# G17_Sensor_V2.net
KiCad netlist of a schematic drawn in EAGLE
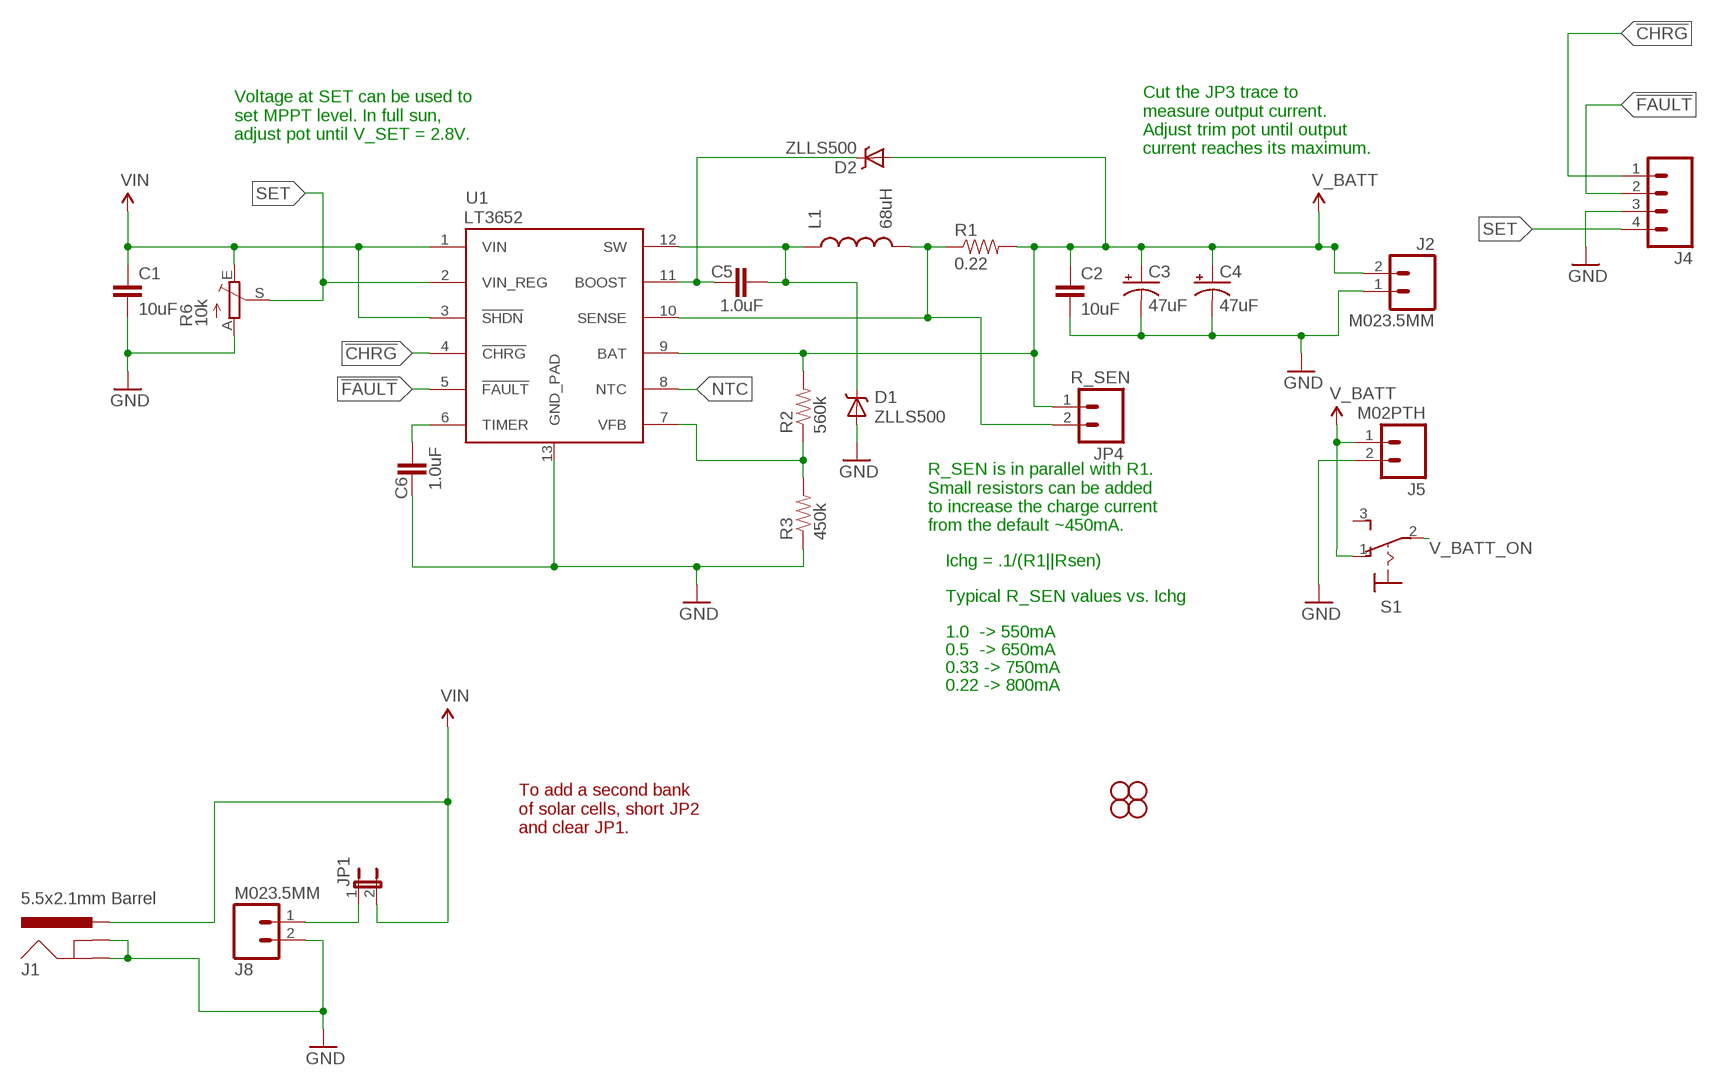
[diagram p0: schematic, sheet 1]
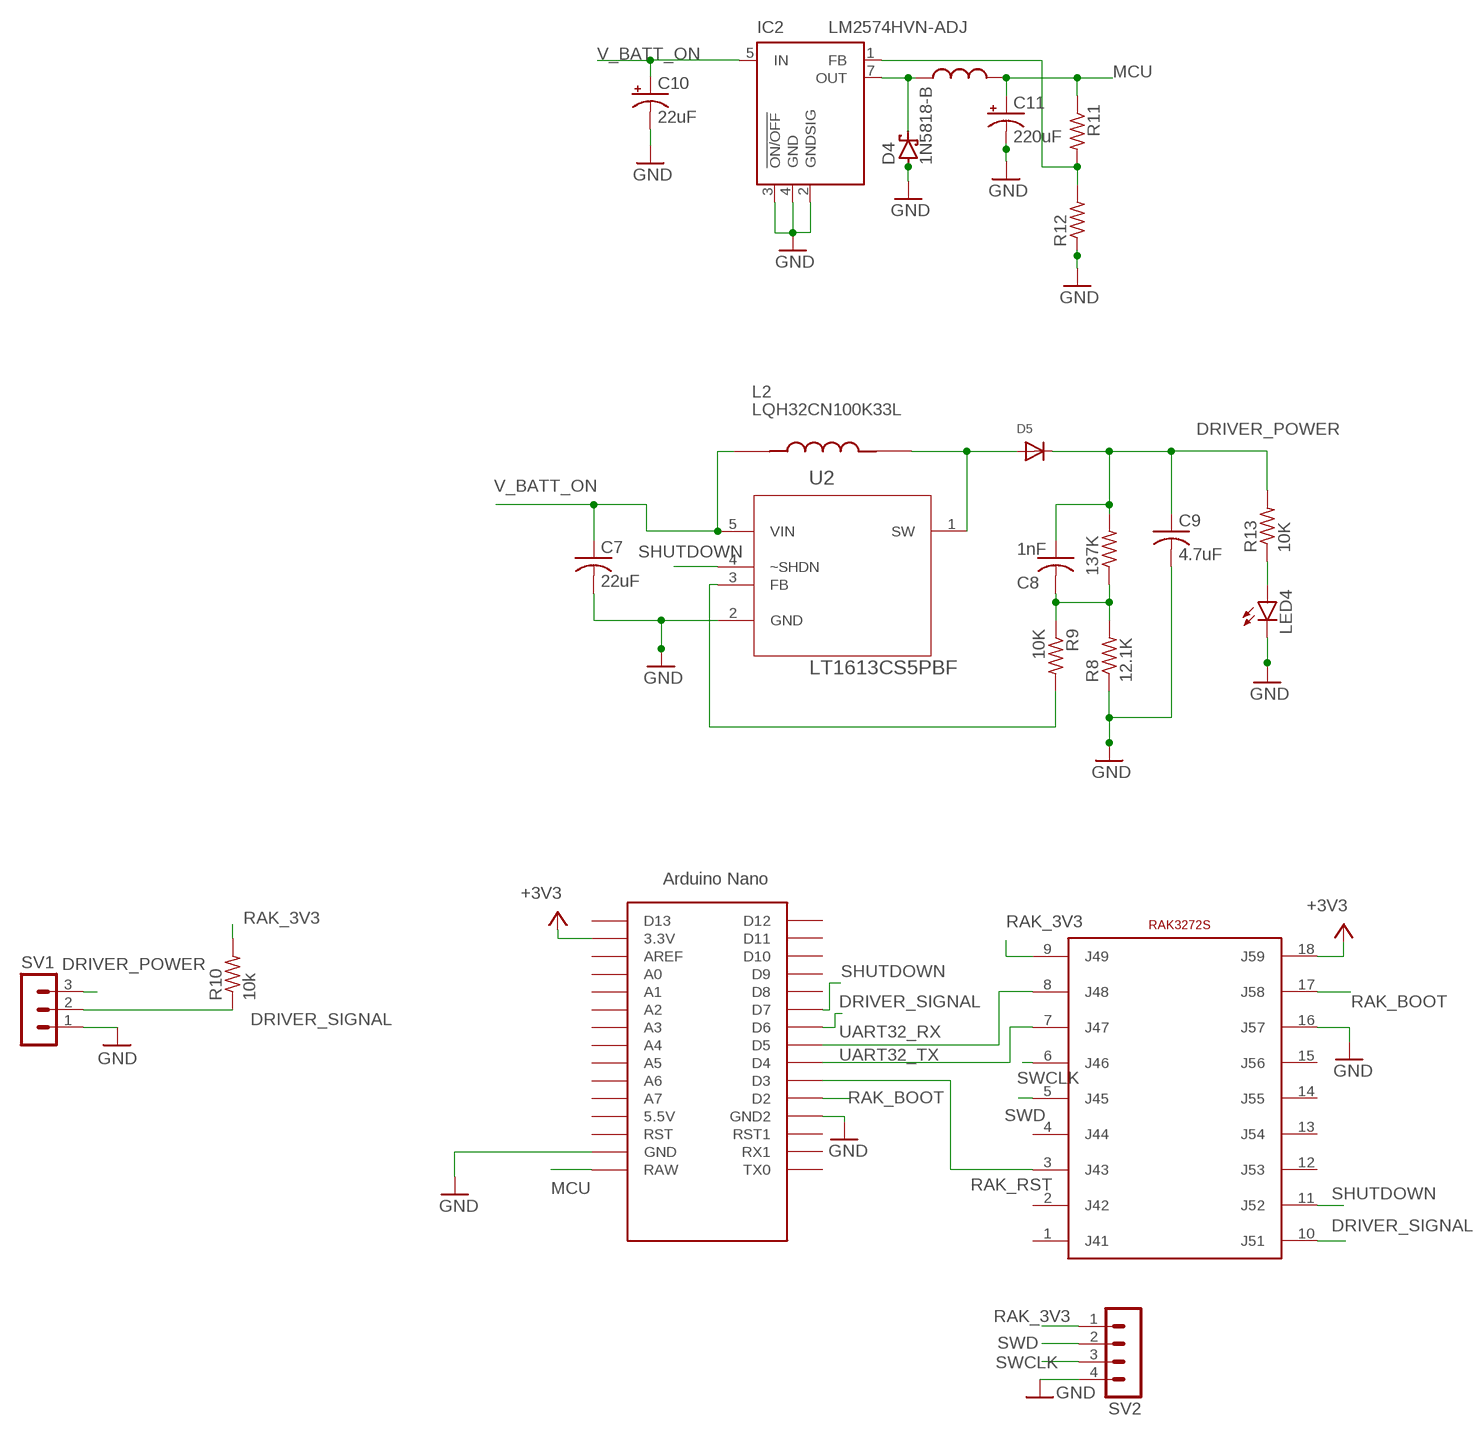
[diagram p1: schematic, sheet 2]

(export (version "E")
  (design (tool "Eeschema 10.0.6"))
  (components
    (comp (ref "137K")
      (value "R-US_R0805")
      (footprint "eagle-import:R0805")
      (libsource (lib "eagle-import") (part "R-US_R0805"))
    )
    (comp (ref "C7")
      (value "22uF")
      (footprint "eagle-import:C0805")
      (libsource (lib "eagle-import") (part "C-USC0805"))
    )
    (comp (ref "C8")
      (value "1nF")
      (footprint "eagle-import:C0805")
      (libsource (lib "eagle-import") (part "C-USC0805"))
    )
    (comp (ref "C9")
      (value "4.7uF")
      (footprint "eagle-import:C1206")
      (libsource (lib "eagle-import") (part "C-USC1206"))
    )
    (comp (ref "C10")
      (value "22uF")
      (footprint "eagle-import:E5-6")
      (libsource (lib "eagle-import") (part "CPOL-USE5-6"))
    )
    (comp (ref "C11")
      (value "220uF")
      (footprint "eagle-import:E5-6")
      (libsource (lib "eagle-import") (part "CPOL-USE5-6"))
    )
    (comp (ref "D4")
      (value "1N5818-B")
      (footprint "eagle-import:DO41-7.6")
      (libsource (lib "eagle-import") (part "1N5818-B"))
    )
    (comp (ref "D5")
      (value "DIODESOD-123")
      (footprint "eagle-import:SOD-123")
      (libsource (lib "eagle-import") (part "DIODESOD-123"))
    )
    (comp (ref "IC2")
      (value "LM2574HVN-ADJ")
      (footprint "eagle-import:DIL08")
      (libsource (lib "eagle-import") (part "LM2574?-HVNADJ"))
    )
    (comp (ref "L2")
      (value "LQH32CN100K33L")
      (footprint "eagle-import:IND_LQH32CN100K33L")
      (fields (field (name "MF") "Murata"))
      (libsource (lib "eagle-import") (part "LQH32CN100K33L"))
    )
    (comp (ref "LED4")
      (value "LED5MM")
      (footprint "eagle-import:LED5MM")
      (libsource (lib "eagle-import") (part "LED5MM"))
    )
    (comp (ref "R8")
      (value "12.1K")
      (footprint "eagle-import:R1206")
      (libsource (lib "eagle-import") (part "R-US_R1206"))
    )
    (comp (ref "R9")
      (value "10K")
      (footprint "eagle-import:R0805")
      (libsource (lib "eagle-import") (part "R-US_R0805"))
    )
    (comp (ref "R10")
      (value "10k")
      (footprint "eagle-import:0204_5")
      (libsource (lib "eagle-import") (part "R-US_0204/5"))
    )
    (comp (ref "R11")
      (value "R-US_0204/7")
      (footprint "eagle-import:0204_7")
      (libsource (lib "eagle-import") (part "R-US_0204/7"))
    )
    (comp (ref "R12")
      (value "R-US_0204/7")
      (footprint "eagle-import:0204_7")
      (libsource (lib "eagle-import") (part "R-US_0204/7"))
    )
    (comp (ref "R13")
      (value "10K")
      (footprint "eagle-import:R0805")
      (libsource (lib "eagle-import") (part "R-US_R0805"))
    )
    (comp (ref "SV1")
      (value "MA03-1")
      (footprint "eagle-import:MA03-1")
      (libsource (lib "eagle-import") (part "MA03-1"))
    )
    (comp (ref "SV2")
      (value "MA04-1")
      (footprint "eagle-import:MA04-1")
      (libsource (lib "eagle-import") (part "MA04-1"))
    )
    (comp (ref "U$1")
      (value "330UH_INDUCTOR")
      (footprint "eagle-import:330UH_INDUCTOR")
      (libsource (lib "eagle-import") (part "330UH_INDUCTOR"))
    )
    (comp (ref "U$3")
      (value "NANO")
      (footprint "eagle-import:NANO")
      (libsource (lib "eagle-import") (part "NANO"))
    )
    (comp (ref "U$4")
      (value "RAK3272S")
      (footprint "eagle-import:RAK3272SFOOTPRINT")
      (libsource (lib "eagle-import") (part "RAK3272S"))
    )
    (comp (ref "U2")
      (value "LT1613CS5PBF")
      (footprint "eagle-import:SOT95P280X145-5N")
      (fields (field (name "MPN") "LT1613CS5#PBF"))
      (libsource (lib "eagle-import") (part "LT1613CS5PBF"))
    )
    (comp (ref "C1")
      (value "10uF")
      (footprint "eagle-import:1210")
      (libsource (lib "eagle-import") (part "10UF50V20%(1210)"))
    )
    (comp (ref "C2")
      (value "10uF")
      (footprint "eagle-import:1206")
      (libsource (lib "eagle-import") (part "10UF-6.3V-20%(1206)"))
    )
    (comp (ref "C3")
      (value "47uF")
      (footprint "eagle-import:EIA3528")
      (libsource (lib "eagle-import") (part "47UF-TANT"))
    )
    (comp (ref "C4")
      (value "47uF")
      (footprint "eagle-import:EIA3528")
      (libsource (lib "eagle-import") (part "47UF-TANT"))
    )
    (comp (ref "C5")
      (value "1.0uF")
      (footprint "eagle-import:0603-CAP")
      (libsource (lib "eagle-import") (part "1.0UF-16V-10%(0603)"))
    )
    (comp (ref "C6")
      (value "1.0uF")
      (footprint "eagle-import:0603-CAP")
      (libsource (lib "eagle-import") (part "1.0UF-16V-10%(0603)"))
    )
    (comp (ref "D1")
      (value "ZLLS500")
      (footprint "eagle-import:SOT23")
      (libsource (lib "eagle-import") (part "ZLLS500ZLLS500"))
    )
    (comp (ref "D2")
      (value "ZLLS500")
      (footprint "eagle-import:SOT23")
      (libsource (lib "eagle-import") (part "ZLLS500ZLLS500"))
    )
    (comp (ref "J1")
      (value "5.5x2.1mm Barrel")
      (footprint "eagle-import:POWER_JACK_SMD")
      (libsource (lib "eagle-import") (part "POWER_JACKSMD"))
    )
    (comp (ref "J2")
      (value "M023.5MM")
      (footprint "eagle-import:SCREWTERMINAL-3.5MM-2")
      (libsource (lib "eagle-import") (part "M023.5MM"))
    )
    (comp (ref "J4")
      (value "M04PTH")
      (footprint "eagle-import:1X04")
      (libsource (lib "eagle-import") (part "M04PTH"))
    )
    (comp (ref "J5")
      (value "M02PTH")
      (footprint "eagle-import:1X02")
      (libsource (lib "eagle-import") (part "M02PTH"))
    )
    (comp (ref "J8")
      (value "M023.5MM")
      (footprint "eagle-import:SCREWTERMINAL-3.5MM-2")
      (libsource (lib "eagle-import") (part "M023.5MM"))
    )
    (comp (ref "JP1")
      (value "JUMPER-2SMD-NC")
      (footprint "eagle-import:SJ_2S")
      (libsource (lib "eagle-import") (part "JUMPER-2SMD-NC"))
    )
    (comp (ref "JP4")
      (value "R_SEN")
      (footprint "eagle-import:1X02")
      (libsource (lib "eagle-import") (part "M02PTH"))
    )
    (comp (ref "L1")
      (value "68uH")
      (footprint "eagle-import:CR75")
      (libsource (lib "eagle-import") (part "INDUCTOR68UH-1A"))
    )
    (comp (ref "R1")
      (value "0.22")
      (footprint "eagle-import:0805")
      (libsource (lib "eagle-import") (part "0.22OHM1/4W1%(0805)"))
    )
    (comp (ref "R2")
      (value "560k")
      (footprint "eagle-import:0603-RES")
      (libsource (lib "eagle-import") (part "47KOHM1/10W1%(0603)"))
    )
    (comp (ref "R3")
      (value "450k")
      (footprint "eagle-import:0603-RES")
      (libsource (lib "eagle-import") (part "220KOHM1/10W1%(0603)"))
    )
    (comp (ref "R6")
      (value "10k")
      (footprint "eagle-import:S63S")
      (libsource (lib "eagle-import") (part "TRIM_EU-S63S"))
    )
    (comp (ref "S1")
      (value "M9040P")
      (footprint "eagle-import:M9040P")
      (libsource (lib "eagle-import") (part "M9040P"))
    )
    (comp (ref "STANDOFF1")
      (value "STAND-OFF")
      (footprint "eagle-import:STAND-OFF")
      (libsource (lib "eagle-import") (part "STAND-OFF"))
    )
    (comp (ref "STANDOFF2")
      (value "STAND-OFF")
      (footprint "eagle-import:STAND-OFF")
      (libsource (lib "eagle-import") (part "STAND-OFF"))
    )
    (comp (ref "STANDOFF3")
      (value "STAND-OFF")
      (footprint "eagle-import:STAND-OFF")
      (libsource (lib "eagle-import") (part "STAND-OFF"))
    )
    (comp (ref "STANDOFF4")
      (value "STAND-OFF")
      (footprint "eagle-import:STAND-OFF")
      (libsource (lib "eagle-import") (part "STAND-OFF"))
    )
    (comp (ref "U1")
      (value "LT3652")
      (footprint "eagle-import:MSOP-12_GND")
      (libsource (lib "eagle-import") (part "LT3652"))
    )
  )
  (nets
    (net (code "1") (name "+3V3") (class "Default")
      (node (ref "U$3") (pin "3.3V") (pinfunction "3.3V_3.3V") (pintype "bidirectional"))
      (node (ref "U$4") (pin "18") (pinfunction "J59_18") (pintype "bidirectional"))
    )
    (net (code "2") (name "DRIVER_POWER") (class "Default")
      (node (ref "137K") (pin "2") (pinfunction "2_2") (pintype "passive"))
      (node (ref "C8") (pin "1") (pinfunction "1_1") (pintype "passive"))
      (node (ref "C9") (pin "1") (pinfunction "1_1") (pintype "passive"))
      (node (ref "D5") (pin "C") (pinfunction "C_C") (pintype "passive"))
      (node (ref "R13") (pin "2") (pinfunction "2_2") (pintype "passive"))
      (node (ref "SV1") (pin "3") (pinfunction "3_3") (pintype "passive"))
    )
    (net (code "3") (name "DRIVER_SIGNAL") (class "Default")
      (node (ref "R10") (pin "1") (pinfunction "1_1") (pintype "passive"))
      (node (ref "SV1") (pin "2") (pinfunction "2_2") (pintype "passive"))
      (node (ref "U$3") (pin "D6") (pinfunction "D6_D6") (pintype "bidirectional"))
      (node (ref "U$4") (pin "10") (pinfunction "J51_10") (pintype "bidirectional"))
    )
    (net (code "4") (name "GND") (class "Default")
      (node (ref "C1") (pin "2") (pinfunction "2_2") (pintype "passive"))
      (node (ref "C10") (pin "-") (pinfunction "-_-") (pintype "passive"))
      (node (ref "C11") (pin "-") (pinfunction "-_-") (pintype "passive"))
      (node (ref "C2") (pin "2") (pinfunction "2_2") (pintype "passive"))
      (node (ref "C3") (pin "C") (pinfunction "-_C") (pintype "passive"))
      (node (ref "C4") (pin "C") (pinfunction "-_C") (pintype "passive"))
      (node (ref "C6") (pin "1") (pinfunction "1_1") (pintype "passive"))
      (node (ref "C7") (pin "2") (pinfunction "2_2") (pintype "passive"))
      (node (ref "C9") (pin "2") (pinfunction "2_2") (pintype "passive"))
      (node (ref "D1") (pin "1") (pinfunction "A_1") (pintype "passive"))
      (node (ref "D4") (pin "A") (pinfunction "A_A") (pintype "passive"))
      (node (ref "IC2") (pin "2") (pinfunction "GNDSIG_2") (pintype "input"))
      (node (ref "IC2") (pin "3") (pinfunction "~{ON/OFF}_3") (pintype "input"))
      (node (ref "IC2") (pin "4") (pinfunction "GND_4") (pintype "power_in"))
      (node (ref "J1") (pin "GND") (pinfunction "GNDBREAK_GND") (pintype "bidirectional"))
      (node (ref "J1") (pin "P$4") (pinfunction "GND_P$4") (pintype "bidirectional"))
      (node (ref "J2") (pin "1") (pinfunction "1_1") (pintype "passive"))
      (node (ref "J4") (pin "3") (pinfunction "3_3") (pintype "passive"))
      (node (ref "J5") (pin "2") (pinfunction "2_2") (pintype "passive"))
      (node (ref "J8") (pin "2") (pinfunction "2_2") (pintype "passive"))
      (node (ref "LED4") (pin "K") (pinfunction "C_K") (pintype "passive"))
      (node (ref "R12") (pin "1") (pinfunction "1_1") (pintype "passive"))
      (node (ref "R3") (pin "1") (pinfunction "1_1") (pintype "passive"))
      (node (ref "R6") (pin "A") (pinfunction "A_A") (pintype "passive"))
      (node (ref "R8") (pin "1") (pinfunction "1_1") (pintype "passive"))
      (node (ref "SV1") (pin "1") (pinfunction "1_1") (pintype "passive"))
      (node (ref "SV2") (pin "4") (pinfunction "4_4") (pintype "passive"))
      (node (ref "U$3") (pin "GND") (pinfunction "GND_GND") (pintype "bidirectional"))
      (node (ref "U$3") (pin "GND1") (pinfunction "GND2_GND1") (pintype "bidirectional"))
      (node (ref "U$4") (pin "16") (pinfunction "J57_16") (pintype "bidirectional"))
      (node (ref "U1") (pin "13") (pinfunction "GND_PAD_13") (pintype "bidirectional"))
      (node (ref "U2") (pin "2") (pinfunction "GND_2") (pintype "passive"))
    )
    (net (code "5") (name "MCU") (class "Default")
      (node (ref "C11") (pin "+") (pinfunction "+_+") (pintype "passive"))
      (node (ref "R11") (pin "1") (pinfunction "1_1") (pintype "passive"))
      (node (ref "U$1") (pin "P$2") (pinfunction "P$2_P$2") (pintype "bidirectional"))
      (node (ref "U$3") (pin "RAW") (pinfunction "RAW_RAW") (pintype "bidirectional"))
    )
    (net (code "6") (name "NTC") (class "Default")
      (node (ref "U1") (pin "8") (pinfunction "NTC_8") (pintype "bidirectional"))
    )
    (net (code "7") (name "Net-(137K-Pad1)") (class "Default")
      (node (ref "137K") (pin "1") (pinfunction "1_1") (pintype "passive"))
      (node (ref "C8") (pin "2") (pinfunction "2_2") (pintype "passive"))
      (node (ref "R8") (pin "2") (pinfunction "2_2") (pintype "passive"))
      (node (ref "R9") (pin "1") (pinfunction "1_1") (pintype "passive"))
    )
    (net (code "8") (name "Net-(D1-C)") (class "Default")
      (node (ref "C5") (pin "2") (pinfunction "2_2") (pintype "passive"))
      (node (ref "D1") (pin "3") (pinfunction "C_3") (pintype "passive"))
      (node (ref "L1") (pin "P$1") (pinfunction "1_P$1") (pintype "passive"))
      (node (ref "U1") (pin "12") (pinfunction "SW_12") (pintype "bidirectional"))
    )
    (net (code "9") (name "Net-(D2-C)") (class "Default")
      (node (ref "C5") (pin "1") (pinfunction "1_1") (pintype "passive"))
      (node (ref "D2") (pin "3") (pinfunction "C_3") (pintype "passive"))
      (node (ref "U1") (pin "11") (pinfunction "BOOST_11") (pintype "bidirectional"))
    )
    (net (code "10") (name "Net-(IC2-FB)") (class "Default")
      (node (ref "IC2") (pin "1") (pinfunction "FB_1") (pintype "input"))
      (node (ref "R11") (pin "2") (pinfunction "2_2") (pintype "passive"))
      (node (ref "R12") (pin "2") (pinfunction "2_2") (pintype "passive"))
    )
    (net (code "11") (name "Net-(IC2-OUT)") (class "Default")
      (node (ref "D4") (pin "C") (pinfunction "C_C") (pintype "passive"))
      (node (ref "IC2") (pin "7") (pinfunction "OUT_7") (pintype "passive"))
      (node (ref "U$1") (pin "P$1") (pinfunction "P$1_P$1") (pintype "bidirectional"))
    )
    (net (code "12") (name "Net-(J8-Pad1)") (class "Default")
      (node (ref "J8") (pin "1") (pinfunction "1_1") (pintype "passive"))
      (node (ref "JP1") (pin "1") (pinfunction "1_1") (pintype "passive"))
    )
    (net (code "13") (name "Net-(L1-2)") (class "Default")
      (node (ref "JP4") (pin "2") (pinfunction "2_2") (pintype "passive"))
      (node (ref "L1") (pin "P$2") (pinfunction "2_P$2") (pintype "passive"))
      (node (ref "R1") (pin "1") (pinfunction "1_1") (pintype "passive"))
      (node (ref "U1") (pin "10") (pinfunction "SENSE_10") (pintype "bidirectional"))
    )
    (net (code "14") (name "Net-(LED4-PadA)") (class "Default")
      (node (ref "LED4") (pin "A") (pinfunction "A_A") (pintype "passive"))
      (node (ref "R13") (pin "1") (pinfunction "1_1") (pintype "passive"))
    )
    (net (code "15") (name "Net-(U1-TIMER)") (class "Default")
      (node (ref "C6") (pin "2") (pinfunction "2_2") (pintype "passive"))
      (node (ref "U1") (pin "6") (pinfunction "TIMER_6") (pintype "bidirectional"))
    )
    (net (code "16") (name "Net-(U1-VFB)") (class "Default")
      (node (ref "R2") (pin "1") (pinfunction "1_1") (pintype "passive"))
      (node (ref "R3") (pin "2") (pinfunction "2_2") (pintype "passive"))
      (node (ref "U1") (pin "7") (pinfunction "VFB_7") (pintype "bidirectional"))
    )
    (net (code "17") (name "Net-(U2-FB)") (class "Default")
      (node (ref "R9") (pin "2") (pinfunction "2_2") (pintype "passive"))
      (node (ref "U2") (pin "3") (pinfunction "FB_3") (pintype "input"))
    )
    (net (code "18") (name "Net-(U2-SW)") (class "Default")
      (node (ref "D5") (pin "A") (pinfunction "A_A") (pintype "passive"))
      (node (ref "L2") (pin "2") (pinfunction "2_2") (pintype "passive"))
      (node (ref "U2") (pin "1") (pinfunction "SW_1") (pintype "output"))
    )
    (net (code "19") (name "RAK_3V3") (class "Default")
      (node (ref "R10") (pin "2") (pinfunction "2_2") (pintype "passive"))
      (node (ref "SV2") (pin "1") (pinfunction "1_1") (pintype "passive"))
      (node (ref "U$4") (pin "9") (pinfunction "J49_9") (pintype "bidirectional"))
    )
    (net (code "20") (name "RAK_BOOT") (class "Default")
      (node (ref "U$3") (pin "D2") (pinfunction "D2_D2") (pintype "bidirectional"))
      (node (ref "U$4") (pin "17") (pinfunction "J58_17") (pintype "bidirectional"))
    )
    (net (code "21") (name "RAK_RST") (class "Default")
      (node (ref "U$3") (pin "D3") (pinfunction "D3_D3") (pintype "bidirectional"))
      (node (ref "U$4") (pin "3") (pinfunction "J43_3") (pintype "bidirectional"))
    )
    (net (code "22") (name "SET") (class "Default")
      (node (ref "J4") (pin "4") (pinfunction "4_4") (pintype "passive"))
      (node (ref "R6") (pin "S") (pinfunction "S_S") (pintype "passive"))
      (node (ref "U1") (pin "2") (pinfunction "VIN_REG_2") (pintype "bidirectional"))
    )
    (net (code "23") (name "SHUTDOWN") (class "Default")
      (node (ref "U$3") (pin "D7") (pinfunction "D7_D7") (pintype "bidirectional"))
      (node (ref "U$4") (pin "11") (pinfunction "J52_11") (pintype "bidirectional"))
      (node (ref "U2") (pin "4") (pinfunction "~{SHDN}_4") (pintype "input"))
    )
    (net (code "24") (name "SWCLK") (class "Default")
      (node (ref "SV2") (pin "3") (pinfunction "3_3") (pintype "passive"))
      (node (ref "U$4") (pin "6") (pinfunction "J46_6") (pintype "bidirectional"))
    )
    (net (code "25") (name "SWD") (class "Default")
      (node (ref "SV2") (pin "2") (pinfunction "2_2") (pintype "passive"))
      (node (ref "U$4") (pin "5") (pinfunction "J45_5") (pintype "bidirectional"))
    )
    (net (code "26") (name "UART32_RX") (class "Default")
      (node (ref "U$3") (pin "D5") (pinfunction "D5_D5") (pintype "bidirectional"))
      (node (ref "U$4") (pin "8") (pinfunction "J48_8") (pintype "bidirectional"))
    )
    (net (code "27") (name "UART32_TX") (class "Default")
      (node (ref "U$3") (pin "D4") (pinfunction "D4_D4") (pintype "bidirectional"))
      (node (ref "U$4") (pin "7") (pinfunction "J47_7") (pintype "bidirectional"))
    )
    (net (code "28") (name "VIN") (class "Default")
      (node (ref "C1") (pin "1") (pinfunction "1_1") (pintype "passive"))
      (node (ref "J1") (pin "VIN0") (pinfunction "PWR_VIN0") (pintype "bidirectional"))
      (node (ref "JP1") (pin "2") (pinfunction "2_2") (pintype "passive"))
      (node (ref "R6") (pin "E") (pinfunction "E_E") (pintype "passive"))
      (node (ref "U1") (pin "1") (pinfunction "VIN_1") (pintype "bidirectional"))
      (node (ref "U1") (pin "3") (pinfunction "~{SHDN}_3") (pintype "bidirectional"))
    )
    (net (code "29") (name "V_BATT") (class "Default")
      (node (ref "C2") (pin "1") (pinfunction "1_1") (pintype "passive"))
      (node (ref "C3") (pin "A") (pinfunction "+_A") (pintype "passive"))
      (node (ref "C4") (pin "A") (pinfunction "+_A") (pintype "passive"))
      (node (ref "D2") (pin "1") (pinfunction "A_1") (pintype "passive"))
      (node (ref "J2") (pin "2") (pinfunction "2_2") (pintype "passive"))
      (node (ref "J5") (pin "1") (pinfunction "1_1") (pintype "passive"))
      (node (ref "JP4") (pin "1") (pinfunction "1_1") (pintype "passive"))
      (node (ref "R1") (pin "2") (pinfunction "2_2") (pintype "passive"))
      (node (ref "R2") (pin "2") (pinfunction "2_2") (pintype "passive"))
      (node (ref "S1") (pin "1") (pinfunction "O_1") (pintype "passive"))
      (node (ref "U1") (pin "9") (pinfunction "BAT_9") (pintype "bidirectional"))
    )
    (net (code "30") (name "V_BATT_ON") (class "Default")
      (node (ref "C10") (pin "+") (pinfunction "+_+") (pintype "passive"))
      (node (ref "C7") (pin "1") (pinfunction "1_1") (pintype "passive"))
      (node (ref "IC2") (pin "5") (pinfunction "IN_5") (pintype "input"))
      (node (ref "L2") (pin "1") (pinfunction "1_1") (pintype "passive"))
      (node (ref "S1") (pin "2") (pinfunction "P_2") (pintype "passive"))
      (node (ref "U2") (pin "5") (pinfunction "VIN_5") (pintype "power_in"))
    )
    (net (code "31") (name "unconnected-(S1-S-Pad3)") (class "Default")
      (node (ref "S1") (pin "3") (pinfunction "S_3") (pintype "passive"))
    )
    (net (code "32") (name "unconnected-(U$3-5.5V-Pad5V)") (class "Default")
      (node (ref "U$3") (pin "5V") (pinfunction "5.5V_5V") (pintype "bidirectional"))
    )
    (net (code "33") (name "unconnected-(U$3-PadA0)") (class "Default")
      (node (ref "U$3") (pin "A0") (pinfunction "A0_A0") (pintype "bidirectional"))
    )
    (net (code "34") (name "unconnected-(U$3-PadA1)") (class "Default")
      (node (ref "U$3") (pin "A1") (pinfunction "A1_A1") (pintype "bidirectional"))
    )
    (net (code "35") (name "unconnected-(U$3-PadA2)") (class "Default")
      (node (ref "U$3") (pin "A2") (pinfunction "A2_A2") (pintype "bidirectional"))
    )
    (net (code "36") (name "unconnected-(U$3-PadA3)") (class "Default")
      (node (ref "U$3") (pin "A3") (pinfunction "A3_A3") (pintype "bidirectional"))
    )
    (net (code "37") (name "unconnected-(U$3-PadA4)") (class "Default")
      (node (ref "U$3") (pin "A4") (pinfunction "A4_A4") (pintype "bidirectional"))
    )
    (net (code "38") (name "unconnected-(U$3-PadA5)") (class "Default")
      (node (ref "U$3") (pin "A5") (pinfunction "A5_A5") (pintype "bidirectional"))
    )
    (net (code "39") (name "unconnected-(U$3-PadA6)") (class "Default")
      (node (ref "U$3") (pin "A6") (pinfunction "A6_A6") (pintype "bidirectional"))
    )
    (net (code "40") (name "unconnected-(U$3-PadA7)") (class "Default")
      (node (ref "U$3") (pin "A7") (pinfunction "A7_A7") (pintype "bidirectional"))
    )
    (net (code "41") (name "unconnected-(U$3-PadAREF)") (class "Default")
      (node (ref "U$3") (pin "AREF") (pinfunction "AREF_AREF") (pintype "bidirectional"))
    )
    (net (code "42") (name "unconnected-(U$3-PadD8)") (class "Default")
      (node (ref "U$3") (pin "D8") (pinfunction "D8_D8") (pintype "bidirectional"))
    )
    (net (code "43") (name "unconnected-(U$3-PadD9)") (class "Default")
      (node (ref "U$3") (pin "D9") (pinfunction "D9_D9") (pintype "bidirectional"))
    )
    (net (code "44") (name "unconnected-(U$3-PadD10)") (class "Default")
      (node (ref "U$3") (pin "D10") (pinfunction "D10_D10") (pintype "bidirectional"))
    )
    (net (code "45") (name "unconnected-(U$3-PadD11)") (class "Default")
      (node (ref "U$3") (pin "D11") (pinfunction "D11_D11") (pintype "bidirectional"))
    )
    (net (code "46") (name "unconnected-(U$3-PadD12)") (class "Default")
      (node (ref "U$3") (pin "D12") (pinfunction "D12_D12") (pintype "bidirectional"))
    )
    (net (code "47") (name "unconnected-(U$3-PadD13)") (class "Default")
      (node (ref "U$3") (pin "D13") (pinfunction "D13_D13") (pintype "bidirectional"))
    )
    (net (code "48") (name "unconnected-(U$3-PadICSP1)") (class "Default")
      (node (ref "U$3") (pin "ICSP1") (pinfunction "ICSP1_ICSP1") (pintype "bidirectional"))
    )
    (net (code "49") (name "unconnected-(U$3-PadICSP2)") (class "Default")
      (node (ref "U$3") (pin "ICSP2") (pinfunction "ICSP2_ICSP2") (pintype "bidirectional"))
    )
    (net (code "50") (name "unconnected-(U$3-PadICSP3)") (class "Default")
      (node (ref "U$3") (pin "ICSP3") (pinfunction "ICSP3_ICSP3") (pintype "bidirectional"))
    )
    (net (code "51") (name "unconnected-(U$3-PadICSP4)") (class "Default")
      (node (ref "U$3") (pin "ICSP4") (pinfunction "ICSP4_ICSP4") (pintype "bidirectional"))
    )
    (net (code "52") (name "unconnected-(U$3-PadICSP5)") (class "Default")
      (node (ref "U$3") (pin "ICSP5") (pinfunction "ICSP5_ICSP5") (pintype "bidirectional"))
    )
    (net (code "53") (name "unconnected-(U$3-PadICSP6)") (class "Default")
      (node (ref "U$3") (pin "ICSP6") (pinfunction "ICSP6_ICSP6") (pintype "bidirectional"))
    )
    (net (code "54") (name "unconnected-(U$3-PadRST)") (class "Default")
      (node (ref "U$3") (pin "RST") (pinfunction "RST_RST") (pintype "bidirectional"))
    )
    (net (code "55") (name "unconnected-(U$3-PadRST1)") (class "Default")
      (node (ref "U$3") (pin "RST1") (pinfunction "RST1_RST1") (pintype "bidirectional"))
    )
    (net (code "56") (name "unconnected-(U$3-PadRX1)") (class "Default")
      (node (ref "U$3") (pin "RX1") (pinfunction "RX1_RX1") (pintype "bidirectional"))
    )
    (net (code "57") (name "unconnected-(U$3-PadTX0)") (class "Default")
      (node (ref "U$3") (pin "TX0") (pinfunction "TX0_TX0") (pintype "bidirectional"))
    )
    (net (code "58") (name "unconnected-(U$4-J41-Pad1)") (class "Default")
      (node (ref "U$4") (pin "1") (pinfunction "J41_1") (pintype "bidirectional"))
    )
    (net (code "59") (name "unconnected-(U$4-J42-Pad2)") (class "Default")
      (node (ref "U$4") (pin "2") (pinfunction "J42_2") (pintype "bidirectional"))
    )
    (net (code "60") (name "unconnected-(U$4-J44-Pad4)") (class "Default")
      (node (ref "U$4") (pin "4") (pinfunction "J44_4") (pintype "bidirectional"))
    )
    (net (code "61") (name "unconnected-(U$4-J53-Pad12)") (class "Default")
      (node (ref "U$4") (pin "12") (pinfunction "J53_12") (pintype "bidirectional"))
    )
    (net (code "62") (name "unconnected-(U$4-J54-Pad13)") (class "Default")
      (node (ref "U$4") (pin "13") (pinfunction "J54_13") (pintype "bidirectional"))
    )
    (net (code "63") (name "unconnected-(U$4-J55-Pad14)") (class "Default")
      (node (ref "U$4") (pin "14") (pinfunction "J55_14") (pintype "bidirectional"))
    )
    (net (code "64") (name "unconnected-(U$4-J56-Pad15)") (class "Default")
      (node (ref "U$4") (pin "15") (pinfunction "J56_15") (pintype "bidirectional"))
    )
    (net (code "65") (name "~{CHRG}") (class "Default")
      (node (ref "J4") (pin "1") (pinfunction "1_1") (pintype "passive"))
      (node (ref "U1") (pin "4") (pinfunction "~{CHRG}_4") (pintype "bidirectional"))
    )
    (net (code "66") (name "~{FAULT}") (class "Default")
      (node (ref "J4") (pin "2") (pinfunction "2_2") (pintype "passive"))
      (node (ref "U1") (pin "5") (pinfunction "~{FAULT}_5") (pintype "bidirectional"))
    )
  )
)
